# ads1299.net
KiCad netlist of a schematic drawn in Altium Designer
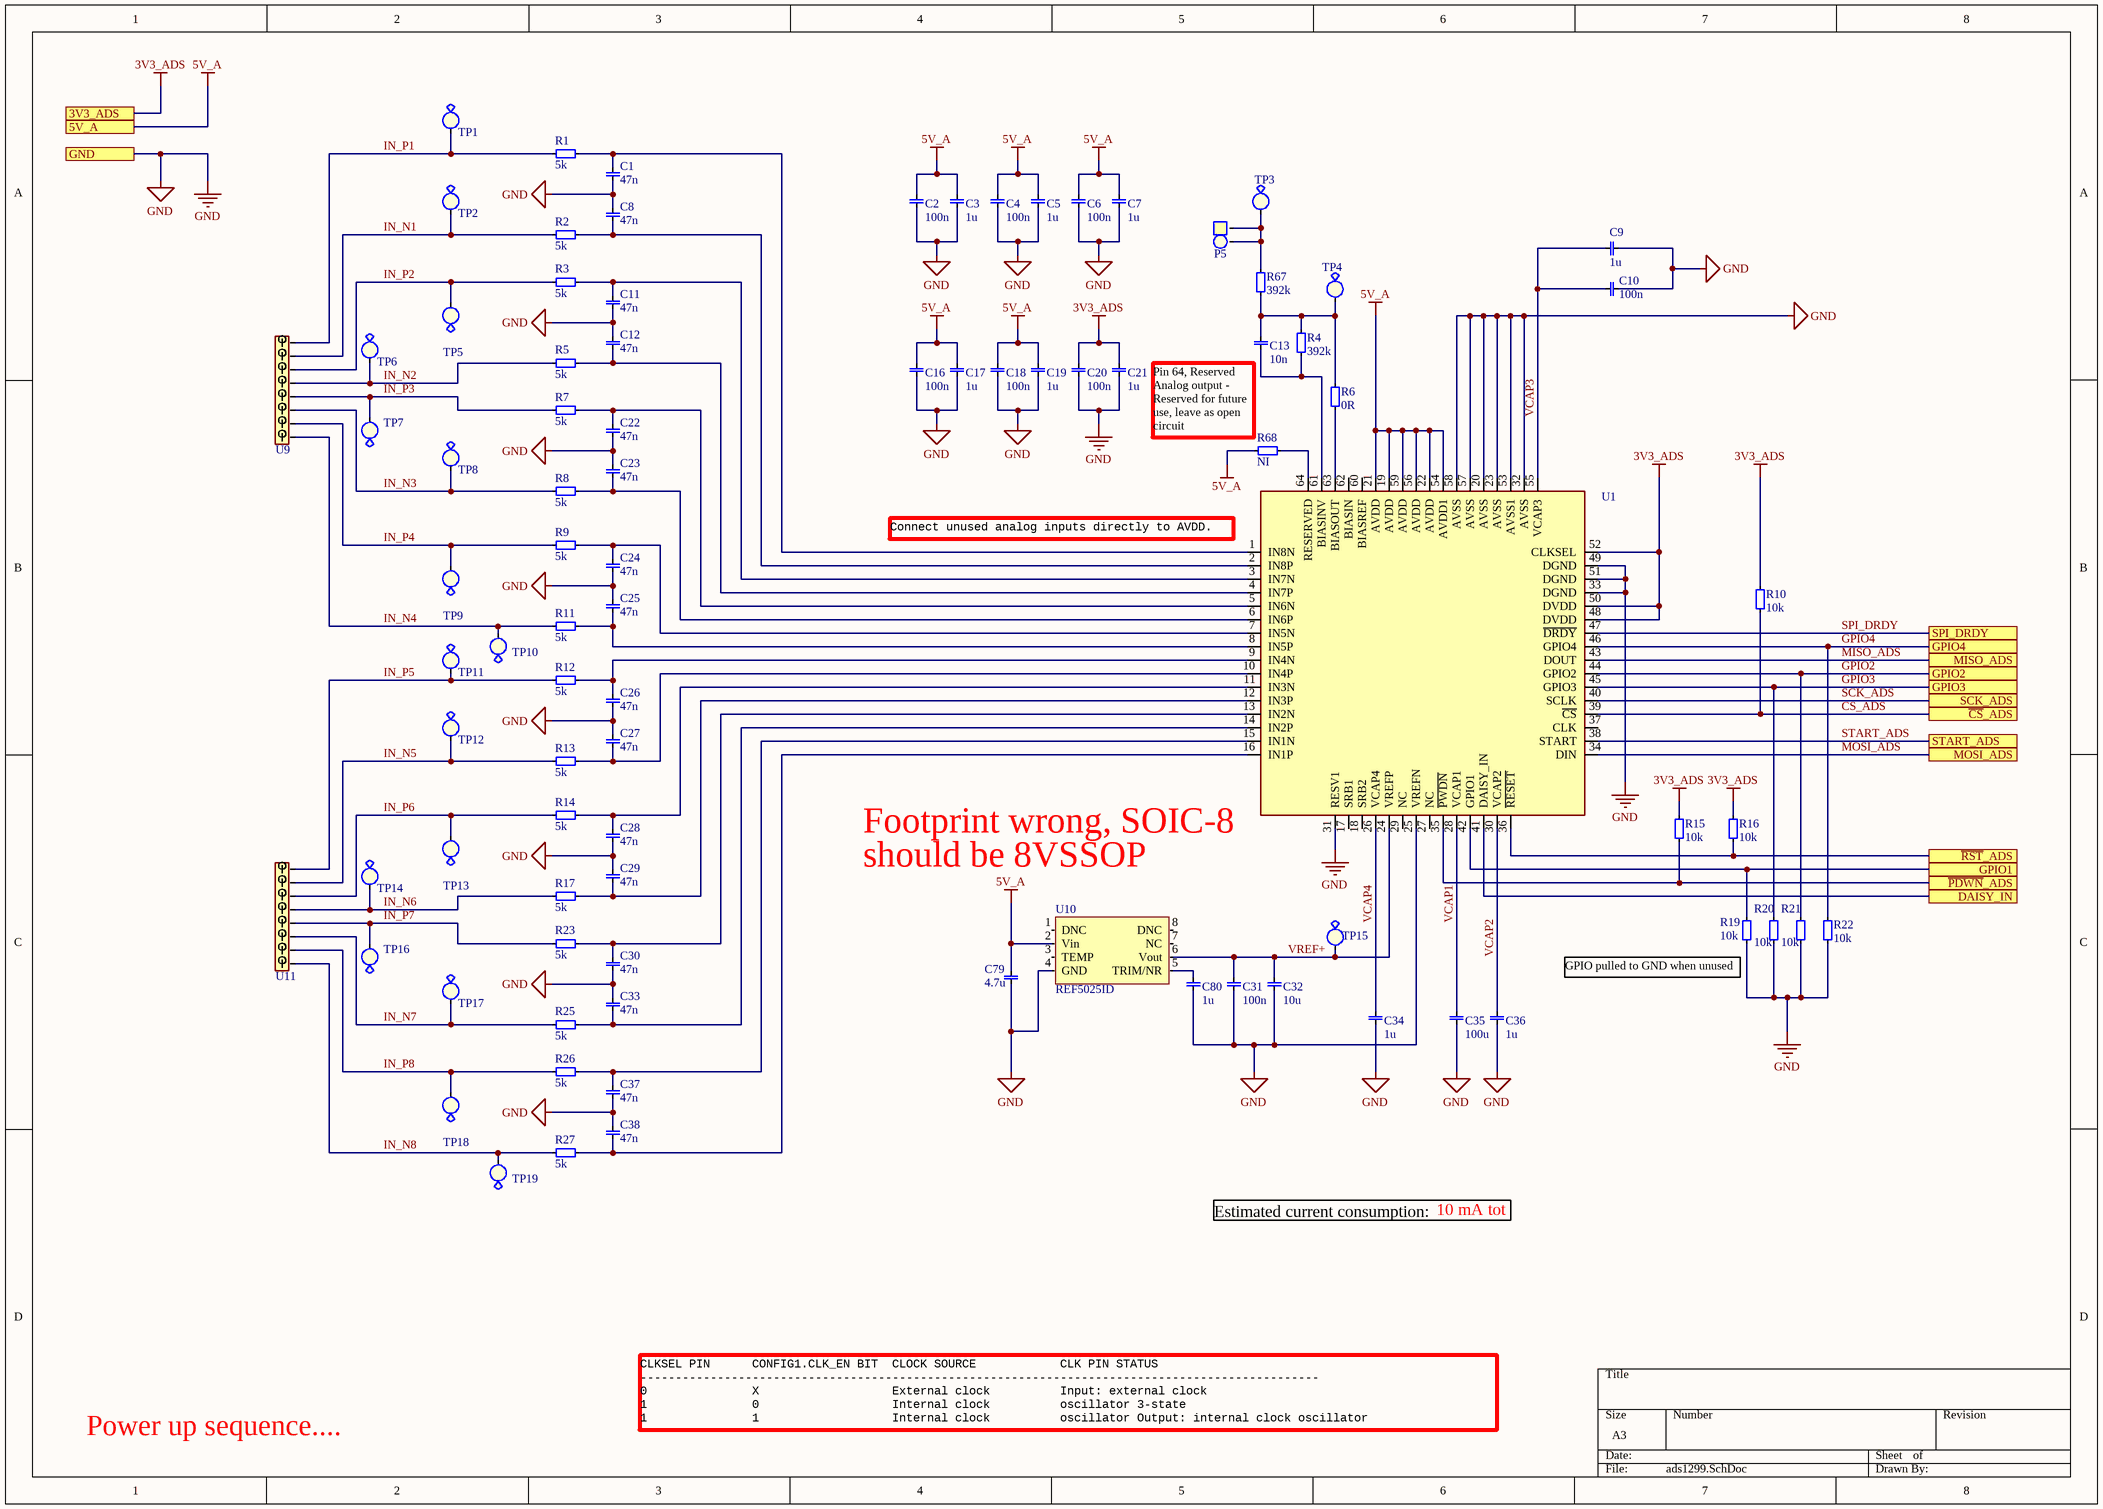
[diagram p0: ads1299.SchDoc]

(export (version "E")
  (design (tool "Eeschema 10.0.6"))
  (components
    (comp (ref "C1")
      (value "47n")
      (footprint "0603 cap")
      (fields (field (name "Comment") "0603, capacitor"))
      (libsource (lib "jclib") (part "0603, capacitor"))
    )
    (comp (ref "C2")
      (value "100n")
      (footprint "0603 cap")
      (description "CAP CER 0.1UF 50V, 10% X7R 0603")
      (fields (field (name "Comment") "0603, capacitor"))
      (libsource (lib "jclib") (part "0603, capacitor"))
    )
    (comp (ref "C3")
      (value "1u")
      (footprint "0603 cap")
      (description "CAP CER 1UF 25V, 10% X5R 0603")
      (fields (field (name "Comment") "0603, capacitor"))
      (libsource (lib "jclib") (part "0603, capacitor"))
    )
    (comp (ref "C4")
      (value "100n")
      (footprint "0603 cap")
      (description "CAP CER 0.1UF 50V, 10% X7R 0603")
      (fields (field (name "Comment") "0603, capacitor"))
      (libsource (lib "jclib") (part "0603, capacitor"))
    )
    (comp (ref "C5")
      (value "1u")
      (footprint "0603 cap")
      (description "CAP CER 1UF 25V, 10% X5R 0603")
      (fields (field (name "Comment") "0603, capacitor"))
      (libsource (lib "jclib") (part "0603, capacitor"))
    )
    (comp (ref "C6")
      (value "100n")
      (footprint "0603 cap")
      (description "CAP CER 0.1UF 50V, 10% X7R 0603")
      (fields (field (name "Comment") "0603, capacitor"))
      (libsource (lib "jclib") (part "0603, capacitor"))
    )
    (comp (ref "C7")
      (value "1u")
      (footprint "0603 cap")
      (description "CAP CER 1UF 25V, 10% X5R 0603")
      (fields (field (name "Comment") "0603, capacitor"))
      (libsource (lib "jclib") (part "0603, capacitor"))
    )
    (comp (ref "C8")
      (value "47n")
      (footprint "0603 cap")
      (fields (field (name "Comment") "0603, capacitor"))
      (libsource (lib "jclib") (part "0603, capacitor"))
    )
    (comp (ref "C9")
      (value "1u")
      (footprint "0603 cap")
      (description "CAP CER 1UF 25V, 10% X5R 0603")
      (fields (field (name "Comment") "0603, capacitor"))
      (libsource (lib "jclib") (part "0603, capacitor"))
    )
    (comp (ref "C10")
      (value "100n")
      (footprint "0603 cap")
      (description "CAP CER 0.1UF 50V, 10% X7R 0603")
      (fields (field (name "Comment") "0603, capacitor"))
      (libsource (lib "jclib") (part "0603, capacitor"))
    )
    (comp (ref "C11")
      (value "47n")
      (footprint "0603 cap")
      (fields (field (name "Comment") "0603, capacitor"))
      (libsource (lib "jclib") (part "0603, capacitor"))
    )
    (comp (ref "C12")
      (value "47n")
      (footprint "0603 cap")
      (fields (field (name "Comment") "0603, capacitor"))
      (libsource (lib "jclib") (part "0603, capacitor"))
    )
    (comp (ref "C13")
      (value "10n")
      (footprint "0603 cap")
      (fields (field (name "Comment") "0603, capacitor"))
      (libsource (lib "jclib") (part "0603, capacitor"))
    )
    (comp (ref "C16")
      (value "100n")
      (footprint "0603 cap")
      (description "CAP CER 0.1UF 50V, 10% X7R 0603")
      (fields (field (name "Comment") "0603, capacitor"))
      (libsource (lib "jclib") (part "0603, capacitor"))
    )
    (comp (ref "C17")
      (value "1u")
      (footprint "0603 cap")
      (description "CAP CER 1UF 25V, 10% X5R 0603")
      (fields (field (name "Comment") "0603, capacitor"))
      (libsource (lib "jclib") (part "0603, capacitor"))
    )
    (comp (ref "C18")
      (value "100n")
      (footprint "0603 cap")
      (description "CAP CER 0.1UF 50V, 10% X7R 0603")
      (fields (field (name "Comment") "0603, capacitor"))
      (libsource (lib "jclib") (part "0603, capacitor"))
    )
    (comp (ref "C19")
      (value "1u")
      (footprint "0603 cap")
      (description "CAP CER 1UF 25V, 10% X5R 0603")
      (fields (field (name "Comment") "0603, capacitor"))
      (libsource (lib "jclib") (part "0603, capacitor"))
    )
    (comp (ref "C20")
      (value "100n")
      (footprint "0603 cap")
      (description "CAP CER 0.1UF 50V, 10% X7R 0603")
      (fields (field (name "Comment") "0603, capacitor"))
      (libsource (lib "jclib") (part "0603, capacitor"))
    )
    (comp (ref "C21")
      (value "1u")
      (footprint "0603 cap")
      (description "CAP CER 1UF 25V, 10% X5R 0603")
      (fields (field (name "Comment") "0603, capacitor"))
      (libsource (lib "jclib") (part "0603, capacitor"))
    )
    (comp (ref "C22")
      (value "47n")
      (footprint "0603 cap")
      (fields (field (name "Comment") "0603, capacitor"))
      (libsource (lib "jclib") (part "0603, capacitor"))
    )
    (comp (ref "C23")
      (value "47n")
      (footprint "0603 cap")
      (fields (field (name "Comment") "0603, capacitor"))
      (libsource (lib "jclib") (part "0603, capacitor"))
    )
    (comp (ref "C24")
      (value "47n")
      (footprint "0603 cap")
      (fields (field (name "Comment") "0603, capacitor"))
      (libsource (lib "jclib") (part "0603, capacitor"))
    )
    (comp (ref "C25")
      (value "47n")
      (footprint "0603 cap")
      (fields (field (name "Comment") "0603, capacitor"))
      (libsource (lib "jclib") (part "0603, capacitor"))
    )
    (comp (ref "C26")
      (value "47n")
      (footprint "0603 cap")
      (fields (field (name "Comment") "0603, capacitor"))
      (libsource (lib "jclib") (part "0603, capacitor"))
    )
    (comp (ref "C27")
      (value "47n")
      (footprint "0603 cap")
      (fields (field (name "Comment") "0603, capacitor"))
      (libsource (lib "jclib") (part "0603, capacitor"))
    )
    (comp (ref "C28")
      (value "47n")
      (footprint "0603 cap")
      (fields (field (name "Comment") "0603, capacitor"))
      (libsource (lib "jclib") (part "0603, capacitor"))
    )
    (comp (ref "C29")
      (value "47n")
      (footprint "0603 cap")
      (fields (field (name "Comment") "0603, capacitor"))
      (libsource (lib "jclib") (part "0603, capacitor"))
    )
    (comp (ref "C30")
      (value "47n")
      (footprint "0603 cap")
      (fields (field (name "Comment") "0603, capacitor"))
      (libsource (lib "jclib") (part "0603, capacitor"))
    )
    (comp (ref "C31")
      (value "100n")
      (footprint "0603 cap")
      (description "CAP CER 0.1UF 50V, 10% X7R 0603")
      (fields (field (name "Comment") "0603, capacitor"))
      (libsource (lib "jclib") (part "0603, capacitor"))
    )
    (comp (ref "C32")
      (value "10u")
      (footprint "0603 cap")
      (description "CAP CER 1UF 25V, 10% X5R 0603")
      (fields (field (name "Comment") "0603, capacitor"))
      (libsource (lib "jclib") (part "0603, capacitor"))
    )
    (comp (ref "C33")
      (value "47n")
      (footprint "0603 cap")
      (fields (field (name "Comment") "0603, capacitor"))
      (libsource (lib "jclib") (part "0603, capacitor"))
    )
    (comp (ref "C34")
      (value "1u")
      (footprint "0603 cap")
      (description "CAP CER 1UF 25V, 10% X5R 0603")
      (fields (field (name "Comment") "0603, capacitor"))
      (libsource (lib "jclib") (part "0603, capacitor"))
    )
    (comp (ref "C35")
      (value "100u")
      (footprint "1210, cap")
      (fields (field (name "Comment") "1210, capacitor"))
      (libsource (lib "jclib") (part "1210, capacitor"))
    )
    (comp (ref "C36")
      (value "1u")
      (footprint "0603 cap")
      (description "CAP CER 1UF 25V, 10% X5R 0603")
      (fields (field (name "Comment") "0603, capacitor"))
      (libsource (lib "jclib") (part "0603, capacitor"))
    )
    (comp (ref "C37")
      (value "47n")
      (footprint "0603 cap")
      (fields (field (name "Comment") "0603, capacitor"))
      (libsource (lib "jclib") (part "0603, capacitor"))
    )
    (comp (ref "C38")
      (value "47n")
      (footprint "0603 cap")
      (fields (field (name "Comment") "0603, capacitor"))
      (libsource (lib "jclib") (part "0603, capacitor"))
    )
    (comp (ref "C79")
      (value "4.7u")
      (footprint "0603 cap")
      (description "CAP CER 1UF 25V, 10% X5R 0603")
      (fields (field (name "Comment") "0603, capacitor"))
      (libsource (lib "jclib") (part "0603, capacitor"))
    )
    (comp (ref "C80")
      (value "1u")
      (footprint "0603 cap")
      (description "CAP CER 1UF 25V, 10% X5R 0603")
      (fields (field (name "Comment") "0603, capacitor"))
      (libsource (lib "jclib") (part "0603, capacitor"))
    )
    (comp (ref "P5")
      (value "1x2 Pin Header")
      (footprint "padtwo_L")
      (description "2.54 mm, TH")
      (libsource (lib "jclib") (part "1x2 Pin Header"))
    )
    (comp (ref "R1")
      (value "5k")
      (footprint "0603")
      (fields (field (name "Comment") "0603, resistor"))
      (libsource (lib "jclib") (part "0603, resistor"))
    )
    (comp (ref "R2")
      (value "5k")
      (footprint "0603")
      (fields (field (name "Comment") "0603, resistor"))
      (libsource (lib "jclib") (part "0603, resistor"))
    )
    (comp (ref "R3")
      (value "5k")
      (footprint "0603")
      (fields (field (name "Comment") "0603, resistor"))
      (libsource (lib "jclib") (part "0603, resistor"))
    )
    (comp (ref "R4")
      (value "392k")
      (footprint "0603")
      (fields (field (name "Comment") "0603, resistor"))
      (libsource (lib "jclib") (part "0603, resistor"))
    )
    (comp (ref "R5")
      (value "5k")
      (footprint "0603")
      (fields (field (name "Comment") "0603, resistor"))
      (libsource (lib "jclib") (part "0603, resistor"))
    )
    (comp (ref "R6")
      (value "0R")
      (footprint "0603")
      (fields (field (name "Comment") "0603, resistor"))
      (libsource (lib "jclib") (part "0603, resistor"))
    )
    (comp (ref "R7")
      (value "5k")
      (footprint "0603")
      (fields (field (name "Comment") "0603, resistor"))
      (libsource (lib "jclib") (part "0603, resistor"))
    )
    (comp (ref "R8")
      (value "5k")
      (footprint "0603")
      (fields (field (name "Comment") "0603, resistor"))
      (libsource (lib "jclib") (part "0603, resistor"))
    )
    (comp (ref "R9")
      (value "5k")
      (footprint "0603")
      (fields (field (name "Comment") "0603, resistor"))
      (libsource (lib "jclib") (part "0603, resistor"))
    )
    (comp (ref "R10")
      (value "10k")
      (footprint "0603")
      (fields (field (name "Comment") "0603, resistor"))
      (libsource (lib "jclib") (part "0603, resistor"))
    )
    (comp (ref "R11")
      (value "5k")
      (footprint "0603")
      (fields (field (name "Comment") "0603, resistor"))
      (libsource (lib "jclib") (part "0603, resistor"))
    )
    (comp (ref "R12")
      (value "5k")
      (footprint "0603")
      (fields (field (name "Comment") "0603, resistor"))
      (libsource (lib "jclib") (part "0603, resistor"))
    )
    (comp (ref "R13")
      (value "5k")
      (footprint "0603")
      (fields (field (name "Comment") "0603, resistor"))
      (libsource (lib "jclib") (part "0603, resistor"))
    )
    (comp (ref "R14")
      (value "5k")
      (footprint "0603")
      (fields (field (name "Comment") "0603, resistor"))
      (libsource (lib "jclib") (part "0603, resistor"))
    )
    (comp (ref "R15")
      (value "10k")
      (footprint "0603")
      (fields (field (name "Comment") "0603, resistor"))
      (libsource (lib "jclib") (part "0603, resistor"))
    )
    (comp (ref "R16")
      (value "10k")
      (footprint "0603")
      (fields (field (name "Comment") "0603, resistor"))
      (libsource (lib "jclib") (part "0603, resistor"))
    )
    (comp (ref "R17")
      (value "5k")
      (footprint "0603")
      (fields (field (name "Comment") "0603, resistor"))
      (libsource (lib "jclib") (part "0603, resistor"))
    )
    (comp (ref "R19")
      (value "10k")
      (footprint "0603")
      (fields (field (name "Comment") "0603, resistor"))
      (libsource (lib "jclib") (part "0603, resistor"))
    )
    (comp (ref "R20")
      (value "10k")
      (footprint "0603")
      (fields (field (name "Comment") "0603, resistor"))
      (libsource (lib "jclib") (part "0603, resistor"))
    )
    (comp (ref "R21")
      (value "10k")
      (footprint "0603")
      (fields (field (name "Comment") "0603, resistor"))
      (libsource (lib "jclib") (part "0603, resistor"))
    )
    (comp (ref "R22")
      (value "10k")
      (footprint "0603")
      (fields (field (name "Comment") "0603, resistor"))
      (libsource (lib "jclib") (part "0603, resistor"))
    )
    (comp (ref "R23")
      (value "5k")
      (footprint "0603")
      (fields (field (name "Comment") "0603, resistor"))
      (libsource (lib "jclib") (part "0603, resistor"))
    )
    (comp (ref "R25")
      (value "5k")
      (footprint "0603")
      (fields (field (name "Comment") "0603, resistor"))
      (libsource (lib "jclib") (part "0603, resistor"))
    )
    (comp (ref "R26")
      (value "5k")
      (footprint "0603")
      (fields (field (name "Comment") "0603, resistor"))
      (libsource (lib "jclib") (part "0603, resistor"))
    )
    (comp (ref "R27")
      (value "5k")
      (footprint "0603")
      (fields (field (name "Comment") "0603, resistor"))
      (libsource (lib "jclib") (part "0603, resistor"))
    )
    (comp (ref "R67")
      (value "392k")
      (footprint "0603")
      (fields (field (name "Comment") "0603, resistor"))
      (libsource (lib "jclib") (part "0603, resistor"))
    )
    (comp (ref "R68")
      (value "NI")
      (footprint "0603")
      (fields (field (name "Comment") "0603, resistor"))
      (libsource (lib "jclib") (part "0603, resistor"))
    )
    (comp (ref "TP1")
      (value "Test Point")
      (footprint "testPoint")
      (libsource (lib "jclib") (part "Test Point"))
    )
    (comp (ref "TP2")
      (value "Test Point")
      (footprint "testPoint")
      (libsource (lib "jclib") (part "Test Point"))
    )
    (comp (ref "TP3")
      (value "Test Point")
      (footprint "testPoint")
      (libsource (lib "jclib") (part "Test Point"))
    )
    (comp (ref "TP4")
      (value "Test Point")
      (footprint "testPoint")
      (libsource (lib "jclib") (part "Test Point"))
    )
    (comp (ref "TP5")
      (value "Test Point")
      (footprint "testPoint")
      (libsource (lib "jclib") (part "Test Point"))
    )
    (comp (ref "TP6")
      (value "Test Point")
      (footprint "testPoint")
      (libsource (lib "jclib") (part "Test Point"))
    )
    (comp (ref "TP7")
      (value "Test Point")
      (footprint "testPoint")
      (libsource (lib "jclib") (part "Test Point"))
    )
    (comp (ref "TP8")
      (value "Test Point")
      (footprint "testPoint")
      (libsource (lib "jclib") (part "Test Point"))
    )
    (comp (ref "TP9")
      (value "Test Point")
      (footprint "testPoint")
      (libsource (lib "jclib") (part "Test Point"))
    )
    (comp (ref "TP10")
      (value "Test Point")
      (footprint "testPoint")
      (libsource (lib "jclib") (part "Test Point"))
    )
    (comp (ref "TP11")
      (value "Test Point")
      (footprint "testPoint")
      (libsource (lib "jclib") (part "Test Point"))
    )
    (comp (ref "TP12")
      (value "Test Point")
      (footprint "testPoint")
      (libsource (lib "jclib") (part "Test Point"))
    )
    (comp (ref "TP13")
      (value "Test Point")
      (footprint "testPoint")
      (libsource (lib "jclib") (part "Test Point"))
    )
    (comp (ref "TP14")
      (value "Test Point")
      (footprint "testPoint")
      (libsource (lib "jclib") (part "Test Point"))
    )
    (comp (ref "TP15")
      (value "Test Point")
      (footprint "testPoint")
      (libsource (lib "jclib") (part "Test Point"))
    )
    (comp (ref "TP16")
      (value "Test Point")
      (footprint "testPoint")
      (libsource (lib "jclib") (part "Test Point"))
    )
    (comp (ref "TP17")
      (value "Test Point")
      (footprint "testPoint")
      (libsource (lib "jclib") (part "Test Point"))
    )
    (comp (ref "TP18")
      (value "Test Point")
      (footprint "testPoint")
      (libsource (lib "jclib") (part "Test Point"))
    )
    (comp (ref "TP19")
      (value "Test Point")
      (footprint "testPoint")
      (libsource (lib "jclib") (part "Test Point"))
    )
    (comp (ref "U1")
      (value "ADS1299")
      (footprint "TQFP64_05MM_P")
      (description "24-Bit, Analog-to-Digital Converter for EEG and\r\nBiopotential Measurements")
      (libsource (lib "jclib") (part "ADS1299"))
    )
    (comp (ref "U9")
      (value "1x8 Screw terminal")
      (footprint "screw_term_8_pos")
      (libsource (lib "jclib") (part "1x8 Screw terminal"))
    )
    (comp (ref "U10") (value "REF5025ID") (footprint "SOIC8") (libsource (lib "jclib") (part "REF5025ID")))
    (comp (ref "U11")
      (value "1x8 Screw terminal")
      (footprint "screw_term_8_pos")
      (libsource (lib "jclib") (part "1x8 Screw terminal"))
    )
  )
  (nets
    (net (code "1") (name "/DAISY_IN") (class "Default")
      (node (ref "U1") (pin "41") (pinfunction "DAISY_IN_41") (pintype "passive"))
    )
    (net (code "2") (name "/GPIO1") (class "Default")
      (node (ref "R19") (pin "0") (pinfunction "0_0") (pintype "passive"))
      (node (ref "U1") (pin "42") (pinfunction "GPIO1_42") (pintype "passive"))
    )
    (net (code "3") (name "/GPIO2") (class "Default")
      (node (ref "R21") (pin "0") (pinfunction "0_0") (pintype "passive"))
      (node (ref "U1") (pin "44") (pinfunction "GPIO2_44") (pintype "passive"))
    )
    (net (code "4") (name "/GPIO3") (class "Default")
      (node (ref "R20") (pin "0") (pinfunction "0_0") (pintype "passive"))
      (node (ref "U1") (pin "45") (pinfunction "GPIO3_45") (pintype "passive"))
    )
    (net (code "5") (name "/GPIO4") (class "Default")
      (node (ref "R22") (pin "0") (pinfunction "0_0") (pintype "passive"))
      (node (ref "U1") (pin "46") (pinfunction "GPIO4_46") (pintype "passive"))
    )
    (net (code "6") (name "/IN_N1") (class "Default")
      (node (ref "R2") (pin "1") (pinfunction "1_1") (pintype "passive"))
      (node (ref "TP2") (pin "0") (pinfunction "0_0") (pintype "passive"))
      (node (ref "U9") (pin "2") (pinfunction "2_2") (pintype "passive"))
    )
    (net (code "7") (name "/IN_N2") (class "Default")
      (node (ref "R5") (pin "1") (pinfunction "1_1") (pintype "passive"))
      (node (ref "TP6") (pin "0") (pinfunction "0_0") (pintype "passive"))
      (node (ref "U9") (pin "4") (pinfunction "4_4") (pintype "passive"))
    )
    (net (code "8") (name "/IN_N3") (class "Default")
      (node (ref "R8") (pin "1") (pinfunction "1_1") (pintype "passive"))
      (node (ref "TP8") (pin "0") (pinfunction "0_0") (pintype "passive"))
      (node (ref "U9") (pin "6") (pinfunction "6_6") (pintype "passive"))
    )
    (net (code "9") (name "/IN_N4") (class "Default")
      (node (ref "R11") (pin "1") (pinfunction "1_1") (pintype "passive"))
      (node (ref "TP10") (pin "0") (pinfunction "0_0") (pintype "passive"))
      (node (ref "U9") (pin "8") (pinfunction "8_8") (pintype "passive"))
    )
    (net (code "10") (name "/IN_N5") (class "Default")
      (node (ref "R13") (pin "1") (pinfunction "1_1") (pintype "passive"))
      (node (ref "TP12") (pin "0") (pinfunction "0_0") (pintype "passive"))
      (node (ref "U11") (pin "2") (pinfunction "2_2") (pintype "passive"))
    )
    (net (code "11") (name "/IN_N6") (class "Default")
      (node (ref "R17") (pin "1") (pinfunction "1_1") (pintype "passive"))
      (node (ref "TP14") (pin "0") (pinfunction "0_0") (pintype "passive"))
      (node (ref "U11") (pin "4") (pinfunction "4_4") (pintype "passive"))
    )
    (net (code "12") (name "/IN_N7") (class "Default")
      (node (ref "R25") (pin "1") (pinfunction "1_1") (pintype "passive"))
      (node (ref "TP17") (pin "0") (pinfunction "0_0") (pintype "passive"))
      (node (ref "U11") (pin "6") (pinfunction "6_6") (pintype "passive"))
    )
    (net (code "13") (name "/IN_N8") (class "Default")
      (node (ref "R27") (pin "1") (pinfunction "1_1") (pintype "passive"))
      (node (ref "TP19") (pin "0") (pinfunction "0_0") (pintype "passive"))
      (node (ref "U11") (pin "8") (pinfunction "8_8") (pintype "passive"))
    )
    (net (code "14") (name "/IN_P1") (class "Default")
      (node (ref "R1") (pin "1") (pinfunction "1_1") (pintype "passive"))
      (node (ref "TP1") (pin "0") (pinfunction "0_0") (pintype "passive"))
      (node (ref "U9") (pin "1") (pinfunction "1_1") (pintype "passive"))
    )
    (net (code "15") (name "/IN_P2") (class "Default")
      (node (ref "R3") (pin "1") (pinfunction "1_1") (pintype "passive"))
      (node (ref "TP5") (pin "0") (pinfunction "0_0") (pintype "passive"))
      (node (ref "U9") (pin "3") (pinfunction "3_3") (pintype "passive"))
    )
    (net (code "16") (name "/IN_P3") (class "Default")
      (node (ref "R7") (pin "1") (pinfunction "1_1") (pintype "passive"))
      (node (ref "TP7") (pin "0") (pinfunction "0_0") (pintype "passive"))
      (node (ref "U9") (pin "5") (pinfunction "5_5") (pintype "passive"))
    )
    (net (code "17") (name "/IN_P4") (class "Default")
      (node (ref "R9") (pin "1") (pinfunction "1_1") (pintype "passive"))
      (node (ref "TP9") (pin "0") (pinfunction "0_0") (pintype "passive"))
      (node (ref "U9") (pin "7") (pinfunction "7_7") (pintype "passive"))
    )
    (net (code "18") (name "/IN_P5") (class "Default")
      (node (ref "R12") (pin "1") (pinfunction "1_1") (pintype "passive"))
      (node (ref "TP11") (pin "0") (pinfunction "0_0") (pintype "passive"))
      (node (ref "U11") (pin "1") (pinfunction "1_1") (pintype "passive"))
    )
    (net (code "19") (name "/IN_P6") (class "Default")
      (node (ref "R14") (pin "1") (pinfunction "1_1") (pintype "passive"))
      (node (ref "TP13") (pin "0") (pinfunction "0_0") (pintype "passive"))
      (node (ref "U11") (pin "3") (pinfunction "3_3") (pintype "passive"))
    )
    (net (code "20") (name "/IN_P7") (class "Default")
      (node (ref "R23") (pin "1") (pinfunction "1_1") (pintype "passive"))
      (node (ref "TP16") (pin "0") (pinfunction "0_0") (pintype "passive"))
      (node (ref "U11") (pin "5") (pinfunction "5_5") (pintype "passive"))
    )
    (net (code "21") (name "/IN_P8") (class "Default")
      (node (ref "R26") (pin "1") (pinfunction "1_1") (pintype "passive"))
      (node (ref "TP18") (pin "0") (pinfunction "0_0") (pintype "passive"))
      (node (ref "U11") (pin "7") (pinfunction "7_7") (pintype "passive"))
    )
    (net (code "22") (name "/MISO_ADS") (class "Default")
      (node (ref "U1") (pin "43") (pinfunction "DOUT_43") (pintype "passive"))
    )
    (net (code "23") (name "/MOSI_ADS") (class "Default")
      (node (ref "U1") (pin "34") (pinfunction "DIN_34") (pintype "passive"))
    )
    (net (code "24") (name "/SCK_ADS") (class "Default")
      (node (ref "U1") (pin "40") (pinfunction "SCLK_40") (pintype "passive"))
    )
    (net (code "25") (name "/SPI_DRDY") (class "Default")
      (node (ref "U1") (pin "47") (pinfunction "~{DRDY}_47") (pintype "passive"))
    )
    (net (code "26") (name "/START_ADS") (class "Default")
      (node (ref "U1") (pin "38") (pinfunction "START_38") (pintype "passive"))
    )
    (net (code "27") (name "/VCAP1") (class "Default")
      (node (ref "C35") (pin "1") (pinfunction "1_1") (pintype "passive"))
      (node (ref "U1") (pin "28") (pinfunction "VCAP1_28") (pintype "passive"))
    )
    (net (code "28") (name "/VCAP2") (class "Default")
      (node (ref "C36") (pin "1") (pinfunction "1_1") (pintype "passive"))
      (node (ref "U1") (pin "30") (pinfunction "VCAP2_30") (pintype "passive"))
    )
    (net (code "29") (name "/VCAP3") (class "Default")
      (node (ref "C10") (pin "1") (pinfunction "1_1") (pintype "passive"))
      (node (ref "C9") (pin "1") (pinfunction "1_1") (pintype "passive"))
      (node (ref "U1") (pin "55") (pinfunction "VCAP3_55") (pintype "passive"))
    )
    (net (code "30") (name "/VCAP4") (class "Default")
      (node (ref "C34") (pin "1") (pinfunction "1_1") (pintype "passive"))
      (node (ref "U1") (pin "26") (pinfunction "VCAP4_26") (pintype "passive"))
    )
    (net (code "31") (name "/VREF+") (class "Default")
      (node (ref "C31") (pin "1") (pinfunction "1_1") (pintype "passive"))
      (node (ref "C32") (pin "1") (pinfunction "1_1") (pintype "passive"))
      (node (ref "TP15") (pin "0") (pinfunction "0_0") (pintype "passive"))
      (node (ref "U1") (pin "24") (pinfunction "VREFP_24") (pintype "passive"))
      (node (ref "U10") (pin "6") (pinfunction "Vout_6") (pintype "passive"))
    )
    (net (code "32") (name "/~{CS}_ADS") (class "Default")
      (node (ref "R10") (pin "1") (pinfunction "1_1") (pintype "passive"))
      (node (ref "U1") (pin "39") (pinfunction "~{CS}_39") (pintype "passive"))
    )
    (net (code "33") (name "/~{PDWN}_ADS") (class "Default")
      (node (ref "R15") (pin "1") (pinfunction "1_1") (pintype "passive"))
      (node (ref "U1") (pin "35") (pinfunction "~{PWDN}_35") (pintype "passive"))
    )
    (net (code "34") (name "/~{RST}_ADS") (class "Default")
      (node (ref "R16") (pin "1") (pinfunction "1_1") (pintype "passive"))
      (node (ref "U1") (pin "36") (pinfunction "~{RESET}_36") (pintype "passive"))
    )
    (net (code "35") (name "3V3_ADS") (class "Default")
      (node (ref "C20") (pin "1") (pinfunction "1_1") (pintype "passive"))
      (node (ref "C21") (pin "1") (pinfunction "1_1") (pintype "passive"))
      (node (ref "R10") (pin "0") (pinfunction "0_0") (pintype "passive"))
      (node (ref "R15") (pin "0") (pinfunction "0_0") (pintype "passive"))
      (node (ref "R16") (pin "0") (pinfunction "0_0") (pintype "passive"))
      (node (ref "U1") (pin "48") (pinfunction "DVDD_48") (pintype "passive"))
      (node (ref "U1") (pin "50") (pinfunction "DVDD_50") (pintype "passive"))
      (node (ref "U1") (pin "52") (pinfunction "CLKSEL_52") (pintype "passive"))
    )
    (net (code "36") (name "5V_A") (class "Default")
      (node (ref "C16") (pin "1") (pinfunction "1_1") (pintype "passive"))
      (node (ref "C17") (pin "1") (pinfunction "1_1") (pintype "passive"))
      (node (ref "C18") (pin "1") (pinfunction "1_1") (pintype "passive"))
      (node (ref "C19") (pin "1") (pinfunction "1_1") (pintype "passive"))
      (node (ref "C2") (pin "1") (pinfunction "1_1") (pintype "passive"))
      (node (ref "C3") (pin "1") (pinfunction "1_1") (pintype "passive"))
      (node (ref "C4") (pin "1") (pinfunction "1_1") (pintype "passive"))
      (node (ref "C5") (pin "1") (pinfunction "1_1") (pintype "passive"))
      (node (ref "C6") (pin "1") (pinfunction "1_1") (pintype "passive"))
      (node (ref "C7") (pin "1") (pinfunction "1_1") (pintype "passive"))
      (node (ref "C79") (pin "1") (pinfunction "1_1") (pintype "passive"))
      (node (ref "R68") (pin "0") (pinfunction "0_0") (pintype "passive"))
      (node (ref "U1") (pin "19") (pinfunction "AVDD_19") (pintype "passive"))
      (node (ref "U1") (pin "21") (pinfunction "AVDD_21") (pintype "passive"))
      (node (ref "U1") (pin "22") (pinfunction "AVDD_22") (pintype "passive"))
      (node (ref "U1") (pin "54") (pinfunction "AVDD1_54") (pintype "passive"))
      (node (ref "U1") (pin "56") (pinfunction "AVDD_56") (pintype "passive"))
      (node (ref "U1") (pin "59") (pinfunction "AVDD_59") (pintype "passive"))
      (node (ref "U10") (pin "2") (pinfunction "Vin_2") (pintype "passive"))
    )
    (net (code "37") (name "GND") (class "Default")
      (node (ref "C1") (pin "0") (pinfunction "0_0") (pintype "passive"))
      (node (ref "C10") (pin "0") (pinfunction "0_0") (pintype "passive"))
      (node (ref "C11") (pin "0") (pinfunction "0_0") (pintype "passive"))
      (node (ref "C12") (pin "0") (pinfunction "0_0") (pintype "passive"))
      (node (ref "C16") (pin "0") (pinfunction "0_0") (pintype "passive"))
      (node (ref "C17") (pin "0") (pinfunction "0_0") (pintype "passive"))
      (node (ref "C18") (pin "0") (pinfunction "0_0") (pintype "passive"))
      (node (ref "C19") (pin "0") (pinfunction "0_0") (pintype "passive"))
      (node (ref "C2") (pin "0") (pinfunction "0_0") (pintype "passive"))
      (node (ref "C20") (pin "0") (pinfunction "0_0") (pintype "passive"))
      (node (ref "C21") (pin "0") (pinfunction "0_0") (pintype "passive"))
      (node (ref "C22") (pin "0") (pinfunction "0_0") (pintype "passive"))
      (node (ref "C23") (pin "0") (pinfunction "0_0") (pintype "passive"))
      (node (ref "C24") (pin "0") (pinfunction "0_0") (pintype "passive"))
      (node (ref "C25") (pin "0") (pinfunction "0_0") (pintype "passive"))
      (node (ref "C26") (pin "0") (pinfunction "0_0") (pintype "passive"))
      (node (ref "C27") (pin "0") (pinfunction "0_0") (pintype "passive"))
      (node (ref "C28") (pin "0") (pinfunction "0_0") (pintype "passive"))
      (node (ref "C29") (pin "0") (pinfunction "0_0") (pintype "passive"))
      (node (ref "C3") (pin "0") (pinfunction "0_0") (pintype "passive"))
      (node (ref "C30") (pin "0") (pinfunction "0_0") (pintype "passive"))
      (node (ref "C31") (pin "0") (pinfunction "0_0") (pintype "passive"))
      (node (ref "C32") (pin "0") (pinfunction "0_0") (pintype "passive"))
      (node (ref "C33") (pin "0") (pinfunction "0_0") (pintype "passive"))
      (node (ref "C34") (pin "0") (pinfunction "0_0") (pintype "passive"))
      (node (ref "C35") (pin "0") (pinfunction "0_0") (pintype "passive"))
      (node (ref "C36") (pin "0") (pinfunction "0_0") (pintype "passive"))
      (node (ref "C37") (pin "0") (pinfunction "0_0") (pintype "passive"))
      (node (ref "C38") (pin "0") (pinfunction "0_0") (pintype "passive"))
      (node (ref "C4") (pin "0") (pinfunction "0_0") (pintype "passive"))
      (node (ref "C5") (pin "0") (pinfunction "0_0") (pintype "passive"))
      (node (ref "C6") (pin "0") (pinfunction "0_0") (pintype "passive"))
      (node (ref "C7") (pin "0") (pinfunction "0_0") (pintype "passive"))
      (node (ref "C79") (pin "0") (pinfunction "0_0") (pintype "passive"))
      (node (ref "C8") (pin "0") (pinfunction "0_0") (pintype "passive"))
      (node (ref "C80") (pin "0") (pinfunction "0_0") (pintype "passive"))
      (node (ref "C9") (pin "0") (pinfunction "0_0") (pintype "passive"))
      (node (ref "R19") (pin "1") (pinfunction "1_1") (pintype "passive"))
      (node (ref "R20") (pin "1") (pinfunction "1_1") (pintype "passive"))
      (node (ref "R21") (pin "1") (pinfunction "1_1") (pintype "passive"))
      (node (ref "R22") (pin "1") (pinfunction "1_1") (pintype "passive"))
      (node (ref "U1") (pin "20") (pinfunction "AVSS_20") (pintype "passive"))
      (node (ref "U1") (pin "23") (pinfunction "AVSS_23") (pintype "passive"))
      (node (ref "U1") (pin "25") (pinfunction "VREFN_25") (pintype "passive"))
      (node (ref "U1") (pin "31") (pinfunction "RESV1_31") (pintype "passive"))
      (node (ref "U1") (pin "32") (pinfunction "AVSS_32") (pintype "passive"))
      (node (ref "U1") (pin "33") (pinfunction "DGND_33") (pintype "passive"))
      (node (ref "U1") (pin "49") (pinfunction "DGND_49") (pintype "passive"))
      (node (ref "U1") (pin "51") (pinfunction "DGND_51") (pintype "passive"))
      (node (ref "U1") (pin "53") (pinfunction "AVSS1_53") (pintype "passive"))
      (node (ref "U1") (pin "57") (pinfunction "AVSS_57") (pintype "passive"))
      (node (ref "U1") (pin "58") (pinfunction "AVSS_58") (pintype "passive"))
      (node (ref "U10") (pin "4") (pinfunction "GND_4") (pintype "passive"))
    )
    (net (code "38") (name "Net-(C13-Pad1)") (class "Default")
      (node (ref "C13") (pin "1") (pinfunction "1_1") (pintype "passive"))
      (node (ref "R4") (pin "0") (pinfunction "0_0") (pintype "passive"))
      (node (ref "R6") (pin "0") (pinfunction "0_0") (pintype "passive"))
      (node (ref "R67") (pin "1") (pinfunction "1_1") (pintype "passive"))
      (node (ref "TP4") (pin "0") (pinfunction "0_0") (pintype "passive"))
    )
    (net (code "39") (name "Net-(P5-Pad1)") (class "Default")
      (node (ref "P5") (pin "1") (pinfunction "1_1") (pintype "passive"))
      (node (ref "P5") (pin "2") (pinfunction "2_2") (pintype "passive"))
      (node (ref "R67") (pin "0") (pinfunction "0_0") (pintype "passive"))
      (node (ref "TP3") (pin "0") (pinfunction "0_0") (pintype "passive"))
    )
    (net (code "40") (name "Net-(U1-BIASINV)") (class "Default")
      (node (ref "C13") (pin "0") (pinfunction "0_0") (pintype "passive"))
      (node (ref "R4") (pin "1") (pinfunction "1_1") (pintype "passive"))
      (node (ref "U1") (pin "61") (pinfunction "BIASINV_61") (pintype "passive"))
    )
    (net (code "41") (name "Net-(U1-BIASOUT)") (class "Default")
      (node (ref "R6") (pin "1") (pinfunction "1_1") (pintype "passive"))
      (node (ref "U1") (pin "63") (pinfunction "BIASOUT_63") (pintype "passive"))
    )
    (net (code "42") (name "Net-(U1-IN1N)") (class "Default")
      (node (ref "C37") (pin "1") (pinfunction "1_1") (pintype "passive"))
      (node (ref "R26") (pin "0") (pinfunction "0_0") (pintype "passive"))
      (node (ref "U1") (pin "15") (pinfunction "IN1N_15") (pintype "passive"))
    )
    (net (code "43") (name "Net-(U1-IN1P)") (class "Default")
      (node (ref "C38") (pin "1") (pinfunction "1_1") (pintype "passive"))
      (node (ref "R27") (pin "0") (pinfunction "0_0") (pintype "passive"))
      (node (ref "U1") (pin "16") (pinfunction "IN1P_16") (pintype "passive"))
    )
    (net (code "44") (name "Net-(U1-IN2N)") (class "Default")
      (node (ref "C30") (pin "1") (pinfunction "1_1") (pintype "passive"))
      (node (ref "R23") (pin "0") (pinfunction "0_0") (pintype "passive"))
      (node (ref "U1") (pin "13") (pinfunction "IN2N_13") (pintype "passive"))
    )
    (net (code "45") (name "Net-(U1-IN2P)") (class "Default")
      (node (ref "C33") (pin "1") (pinfunction "1_1") (pintype "passive"))
      (node (ref "R25") (pin "0") (pinfunction "0_0") (pintype "passive"))
      (node (ref "U1") (pin "14") (pinfunction "IN2P_14") (pintype "passive"))
    )
    (net (code "46") (name "Net-(U1-IN3N)") (class "Default")
      (node (ref "C28") (pin "1") (pinfunction "1_1") (pintype "passive"))
      (node (ref "R14") (pin "0") (pinfunction "0_0") (pintype "passive"))
      (node (ref "U1") (pin "11") (pinfunction "IN3N_11") (pintype "passive"))
    )
    (net (code "47") (name "Net-(U1-IN3P)") (class "Default")
      (node (ref "C29") (pin "1") (pinfunction "1_1") (pintype "passive"))
      (node (ref "R17") (pin "0") (pinfunction "0_0") (pintype "passive"))
      (node (ref "U1") (pin "12") (pinfunction "IN3P_12") (pintype "passive"))
    )
    (net (code "48") (name "Net-(U1-IN4N)") (class "Default")
      (node (ref "C26") (pin "1") (pinfunction "1_1") (pintype "passive"))
      (node (ref "R12") (pin "0") (pinfunction "0_0") (pintype "passive"))
      (node (ref "U1") (pin "9") (pinfunction "IN4N_9") (pintype "passive"))
    )
    (net (code "49") (name "Net-(U1-IN4P)") (class "Default")
      (node (ref "C27") (pin "1") (pinfunction "1_1") (pintype "passive"))
      (node (ref "R13") (pin "0") (pinfunction "0_0") (pintype "passive"))
      (node (ref "U1") (pin "10") (pinfunction "IN4P_10") (pintype "passive"))
    )
    (net (code "50") (name "Net-(U1-IN5N)") (class "Default")
      (node (ref "C24") (pin "1") (pinfunction "1_1") (pintype "passive"))
      (node (ref "R9") (pin "0") (pinfunction "0_0") (pintype "passive"))
      (node (ref "U1") (pin "7") (pinfunction "IN5N_7") (pintype "passive"))
    )
    (net (code "51") (name "Net-(U1-IN5P)") (class "Default")
      (node (ref "C25") (pin "1") (pinfunction "1_1") (pintype "passive"))
      (node (ref "R11") (pin "0") (pinfunction "0_0") (pintype "passive"))
      (node (ref "U1") (pin "8") (pinfunction "IN5P_8") (pintype "passive"))
    )
    (net (code "52") (name "Net-(U1-IN6N)") (class "Default")
      (node (ref "C22") (pin "1") (pinfunction "1_1") (pintype "passive"))
      (node (ref "R7") (pin "0") (pinfunction "0_0") (pintype "passive"))
      (node (ref "U1") (pin "5") (pinfunction "IN6N_5") (pintype "passive"))
    )
    (net (code "53") (name "Net-(U1-IN6P)") (class "Default")
      (node (ref "C23") (pin "1") (pinfunction "1_1") (pintype "passive"))
      (node (ref "R8") (pin "0") (pinfunction "0_0") (pintype "passive"))
      (node (ref "U1") (pin "6") (pinfunction "IN6P_6") (pintype "passive"))
    )
    (net (code "54") (name "Net-(U1-IN7N)") (class "Default")
      (node (ref "C11") (pin "1") (pinfunction "1_1") (pintype "passive"))
      (node (ref "R3") (pin "0") (pinfunction "0_0") (pintype "passive"))
      (node (ref "U1") (pin "3") (pinfunction "IN7N_3") (pintype "passive"))
    )
    (net (code "55") (name "Net-(U1-IN7P)") (class "Default")
      (node (ref "C12") (pin "1") (pinfunction "1_1") (pintype "passive"))
      (node (ref "R5") (pin "0") (pinfunction "0_0") (pintype "passive"))
      (node (ref "U1") (pin "4") (pinfunction "IN7P_4") (pintype "passive"))
    )
    (net (code "56") (name "Net-(U1-IN8N)") (class "Default")
      (node (ref "C1") (pin "1") (pinfunction "1_1") (pintype "passive"))
      (node (ref "R1") (pin "0") (pinfunction "0_0") (pintype "passive"))
      (node (ref "U1") (pin "1") (pinfunction "IN8N_1") (pintype "passive"))
    )
    (net (code "57") (name "Net-(U1-IN8P)") (class "Default")
      (node (ref "C8") (pin "1") (pinfunction "1_1") (pintype "passive"))
      (node (ref "R2") (pin "0") (pinfunction "0_0") (pintype "passive"))
      (node (ref "U1") (pin "2") (pinfunction "IN8P_2") (pintype "passive"))
    )
    (net (code "58") (name "Net-(U1-RESERVED)") (class "Default")
      (node (ref "R68") (pin "1") (pinfunction "1_1") (pintype "passive"))
      (node (ref "U1") (pin "64") (pinfunction "RESERVED_64") (pintype "passive"))
    )
    (net (code "59") (name "Net-(U10-TRIM{slash}NR)") (class "Default")
      (node (ref "C80") (pin "1") (pinfunction "1_1") (pintype "passive"))
      (node (ref "U10") (pin "5") (pinfunction "TRIM/NR_5") (pintype "passive"))
    )
    (net (code "60") (name "unconnected-(U1-BIASIN-Pad62)") (class "Default")
      (node (ref "U1") (pin "62") (pinfunction "BIASIN_62") (pintype "passive"))
    )
    (net (code "61") (name "unconnected-(U1-BIASREF-Pad60)") (class "Default")
      (node (ref "U1") (pin "60") (pinfunction "BIASREF_60") (pintype "passive"))
    )
    (net (code "62") (name "unconnected-(U1-CLK-Pad37)") (class "Default")
      (node (ref "U1") (pin "37") (pinfunction "CLK_37") (pintype "passive"))
    )
    (net (code "63") (name "unconnected-(U1-NC-Pad27)") (class "Default")
      (node (ref "U1") (pin "27") (pinfunction "NC_27") (pintype "passive"))
    )
    (net (code "64") (name "unconnected-(U1-NC-Pad29)") (class "Default")
      (node (ref "U1") (pin "29") (pinfunction "NC_29") (pintype "passive"))
    )
    (net (code "65") (name "unconnected-(U1-SRB1-Pad17)") (class "Default")
      (node (ref "U1") (pin "17") (pinfunction "SRB1_17") (pintype "passive"))
    )
    (net (code "66") (name "unconnected-(U1-SRB2-Pad18)") (class "Default")
      (node (ref "U1") (pin "18") (pinfunction "SRB2_18") (pintype "passive"))
    )
    (net (code "67") (name "unconnected-(U10-DNC-Pad1)") (class "Default")
      (node (ref "U10") (pin "1") (pinfunction "DNC_1") (pintype "passive"))
    )
    (net (code "68") (name "unconnected-(U10-DNC-Pad8)") (class "Default")
      (node (ref "U10") (pin "8") (pinfunction "DNC_8") (pintype "passive"))
    )
    (net (code "69") (name "unconnected-(U10-NC-Pad7)") (class "Default")
      (node (ref "U10") (pin "7") (pinfunction "NC_7") (pintype "passive"))
    )
    (net (code "70") (name "unconnected-(U10-TEMP-Pad3)") (class "Default")
      (node (ref "U10") (pin "3") (pinfunction "TEMP_3") (pintype "passive"))
    )
  )
)
